# amp-PA-TQP7M9105-with-detect.net
KiCad netlist of a schematic drawn in EAGLE
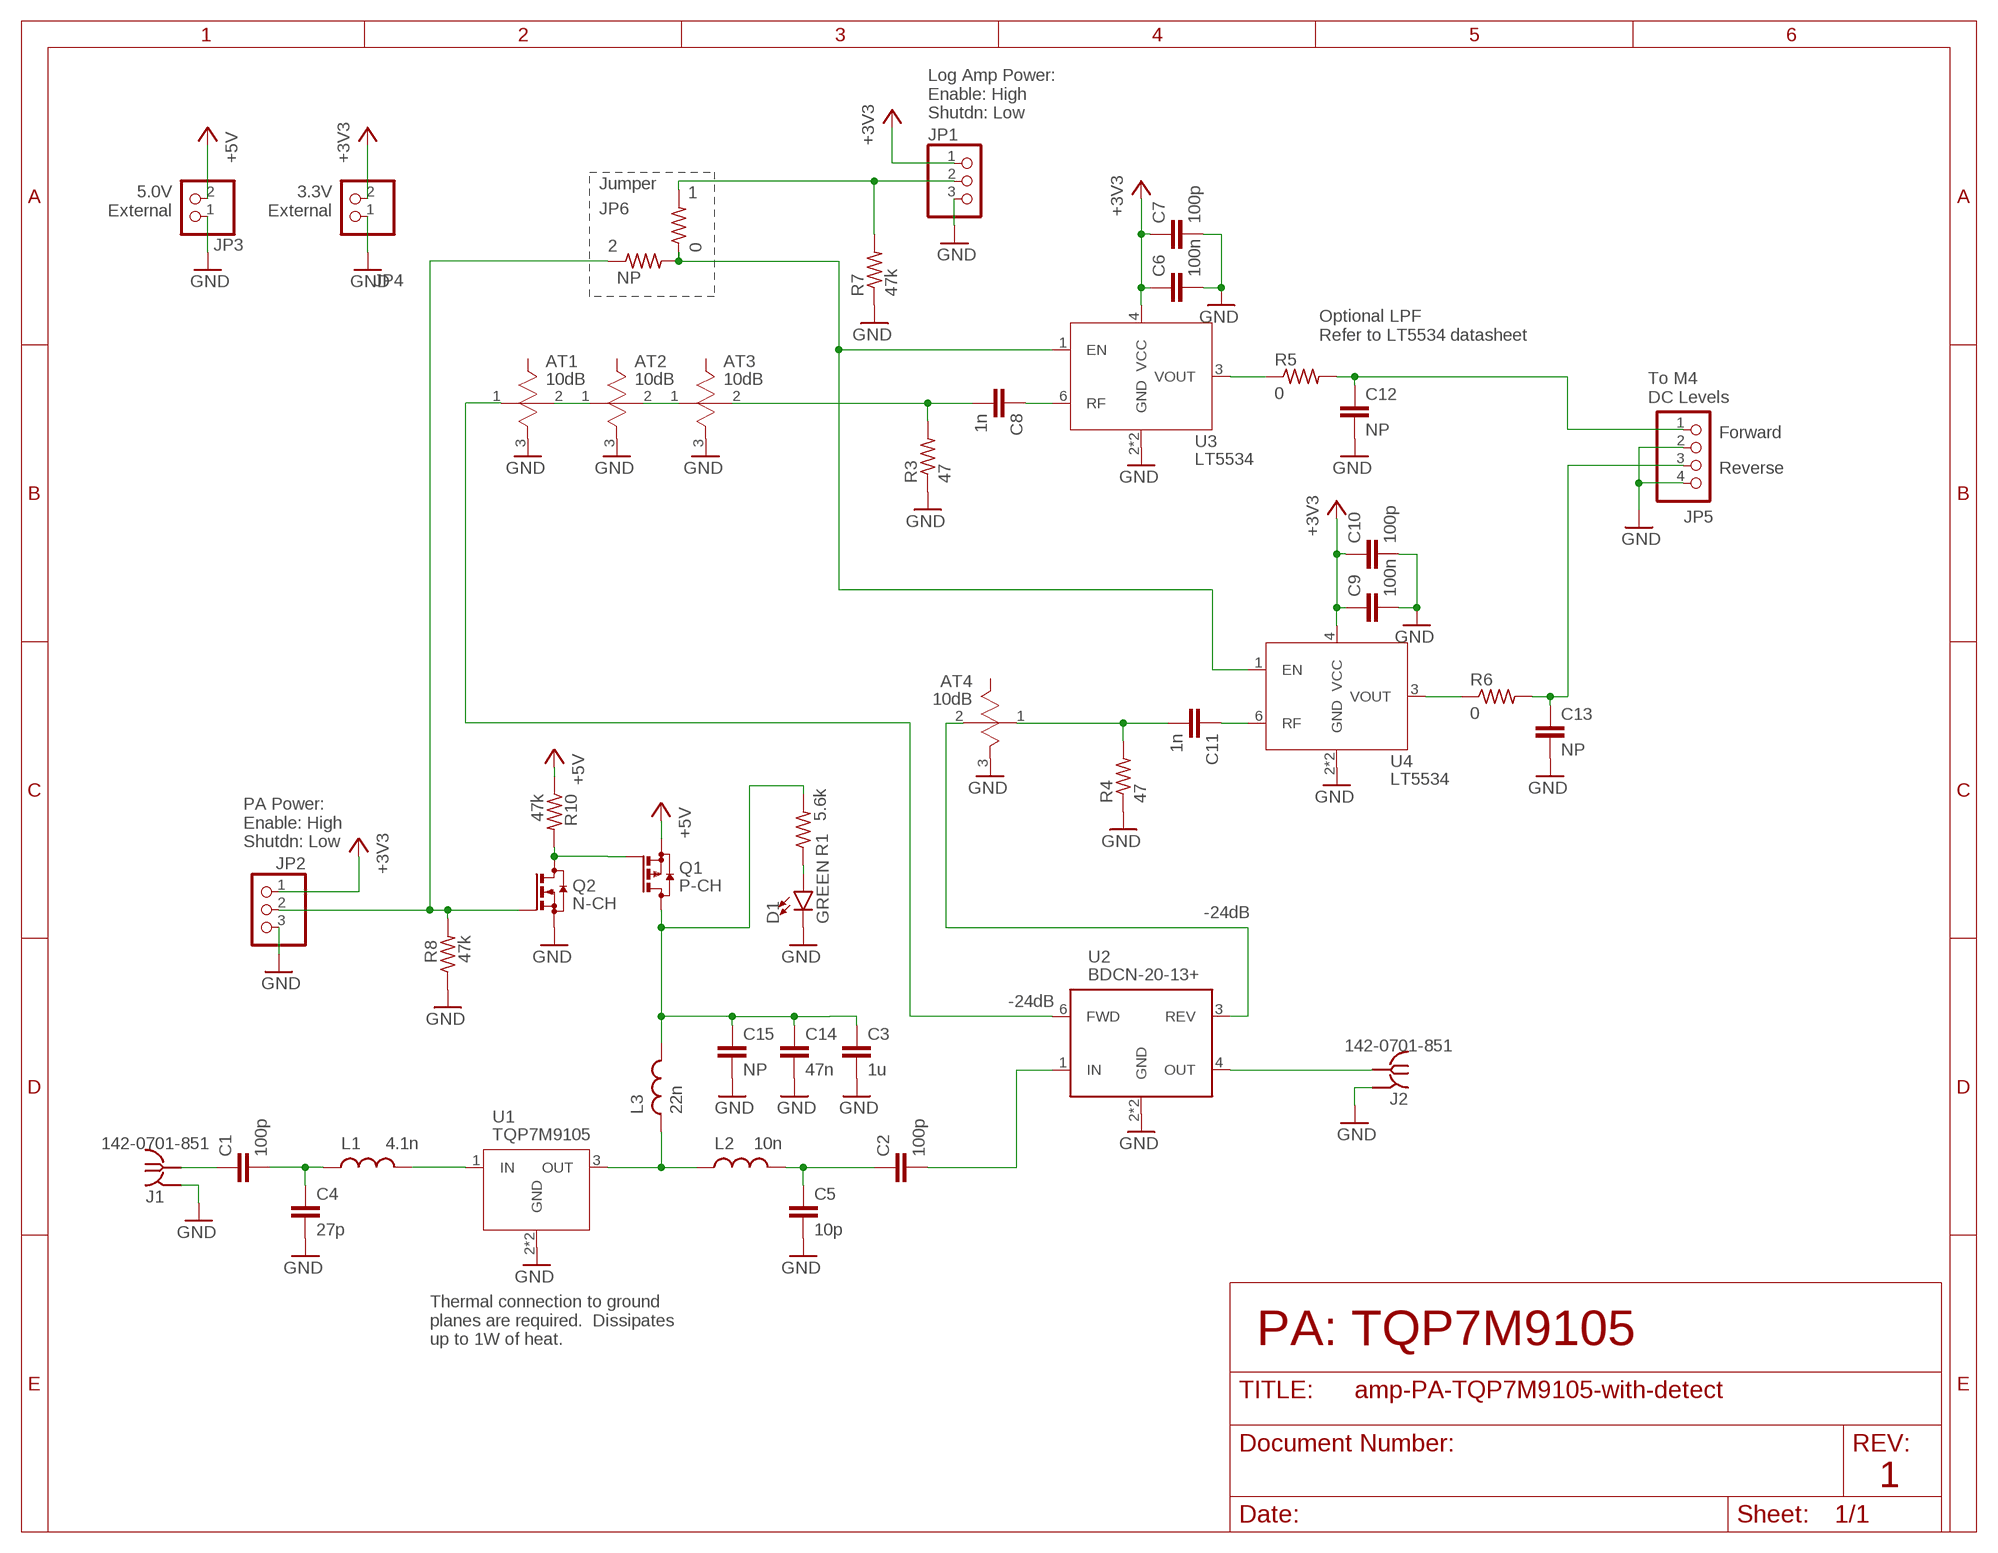
[diagram p0: schematic, sheet 1]

(export (version "E")
  (design (tool "Eeschema 10.0.6"))
  (components
    (comp (ref "AT1")
      (value "10dB")
      (footprint "eagle-import:0805")
      (libsource (lib "eagle-import") (part "PAT1220"))
    )
    (comp (ref "AT2")
      (value "10dB")
      (footprint "eagle-import:0603")
      (libsource (lib "eagle-import") (part "PAT0816"))
    )
    (comp (ref "AT3")
      (value "10dB")
      (footprint "eagle-import:0603")
      (libsource (lib "eagle-import") (part "PAT0816"))
    )
    (comp (ref "AT4")
      (value "10dB")
      (footprint "eagle-import:0603")
      (libsource (lib "eagle-import") (part "PAT0816"))
    )
    (comp (ref "C1")
      (value "100p")
      (footprint "eagle-import:.0402-C-NOSILK")
      (libsource (lib "eagle-import") (part "C-EU0402-C-NOSILK"))
    )
    (comp (ref "C2")
      (value "100p")
      (footprint "eagle-import:.0603-C-NOSILK")
      (libsource (lib "eagle-import") (part "C-EU0603-C-NOSILK"))
    )
    (comp (ref "C3")
      (value "1u")
      (footprint "eagle-import:.0603-B-NOSILK")
      (libsource (lib "eagle-import") (part "C-EU0603-B-NOSILK"))
    )
    (comp (ref "C4")
      (value "27p")
      (footprint "eagle-import:.0402-C-NOSILK")
      (libsource (lib "eagle-import") (part "C-EU0402-C-NOSILK"))
    )
    (comp (ref "C5")
      (value "10p")
      (footprint "eagle-import:.0603-C-NOSILK")
      (libsource (lib "eagle-import") (part "C-EU0603-C-NOSILK"))
    )
    (comp (ref "C6")
      (value "100n")
      (footprint "eagle-import:.0603-B-NOSILK")
      (libsource (lib "eagle-import") (part "C-EU0603-B-NOSILK"))
    )
    (comp (ref "C7")
      (value "100p")
      (footprint "eagle-import:.0603-B-NOSILK")
      (libsource (lib "eagle-import") (part "C-EU0603-B-NOSILK"))
    )
    (comp (ref "C8")
      (value "1n")
      (footprint "eagle-import:.0402-C-NOSILK")
      (libsource (lib "eagle-import") (part "C-EU0402-C-NOSILK"))
    )
    (comp (ref "C9")
      (value "100n")
      (footprint "eagle-import:.0603-B-NOSILK")
      (libsource (lib "eagle-import") (part "C-EU0603-B-NOSILK"))
    )
    (comp (ref "C10")
      (value "100p")
      (footprint "eagle-import:.0603-B-NOSILK")
      (libsource (lib "eagle-import") (part "C-EU0603-B-NOSILK"))
    )
    (comp (ref "C11")
      (value "1n")
      (footprint "eagle-import:.0402-C-NOSILK")
      (libsource (lib "eagle-import") (part "C-EU0402-C-NOSILK"))
    )
    (comp (ref "C12")
      (value "NP")
      (footprint "eagle-import:.0603-B-NOSILK")
      (libsource (lib "eagle-import") (part "C-EU0603-B-NOSILK"))
    )
    (comp (ref "C13")
      (value "NP")
      (footprint "eagle-import:.0603-B-NOSILK")
      (libsource (lib "eagle-import") (part "C-EU0603-B-NOSILK"))
    )
    (comp (ref "C14")
      (value "47n")
      (footprint "eagle-import:.0603-B-NOSILK")
      (libsource (lib "eagle-import") (part "C-EU0603-B-NOSILK"))
    )
    (comp (ref "C15")
      (value "NP")
      (footprint "eagle-import:.0603-B-NOSILK")
      (libsource (lib "eagle-import") (part "C-EU0603-B-NOSILK"))
    )
    (comp (ref "D1")
      (value "GREEN")
      (footprint "eagle-import:LED-0603")
      (libsource (lib "eagle-import") (part "LED-GREEN0603"))
    )
    (comp (ref "J1")
      (value "142-0701-851")
      (footprint "eagle-import:142-0701-851")
      (libsource (lib "eagle-import") (part "142-0701-851"))
    )
    (comp (ref "J2")
      (value "142-0701-851")
      (footprint "eagle-import:142-0701-851")
      (libsource (lib "eagle-import") (part "142-0701-851"))
    )
    (comp (ref "JP1")
      (value "PINHD-1X3")
      (footprint "eagle-import:1X03")
      (libsource (lib "eagle-import") (part "PINHD-1X3"))
    )
    (comp (ref "JP2")
      (value "PINHD-1X3")
      (footprint "eagle-import:1X03")
      (libsource (lib "eagle-import") (part "PINHD-1X3"))
    )
    (comp (ref "JP3")
      (value "PINHD-1X2")
      (footprint "eagle-import:1X02")
      (libsource (lib "eagle-import") (part "PINHD-1X2"))
    )
    (comp (ref "JP4")
      (value "PINHD-1X2")
      (footprint "eagle-import:1X02")
      (libsource (lib "eagle-import") (part "PINHD-1X2"))
    )
    (comp (ref "JP5")
      (value "PINHD-1X4")
      (footprint "eagle-import:1X04")
      (libsource (lib "eagle-import") (part "PINHD-1X4"))
    )
    (comp (ref "JP6")
      (value "NP")
      (footprint "eagle-import:.0603-B-NOSILK")
      (libsource (lib "eagle-import") (part "R-US_0603-B-NOSILK"))
    )
    (comp (ref "L1")
      (value "4.1n")
      (footprint "eagle-import:.0402-C-NOSILK")
      (libsource (lib "eagle-import") (part "L-US0402-C-NOSILK"))
    )
    (comp (ref "L2")
      (value "10n")
      (footprint "eagle-import:.0603-C-NOSILK@1")
      (libsource (lib "eagle-import") (part "L-US0603-C-NOSILK"))
    )
    (comp (ref "L3")
      (value "22n")
      (footprint "eagle-import:.0805-C-NOSILK")
      (libsource (lib "eagle-import") (part "L-US0805-C-NOSILK"))
    )
    (comp (ref "Q1")
      (value "P-CH")
      (footprint "eagle-import:SOT23")
      (libsource (lib "eagle-import") (part "BSS84"))
    )
    (comp (ref "Q2")
      (value "N-CH")
      (footprint "eagle-import:SOT23")
      (libsource (lib "eagle-import") (part "BSS123"))
    )
    (comp (ref "R1")
      (value "5.6k")
      (footprint "eagle-import:.0603-B-NOSILK")
      (libsource (lib "eagle-import") (part "R-US_0603-B-NOSILK"))
    )
    (comp (ref "R3")
      (value "47")
      (footprint "eagle-import:.0402-C-NOSILK")
      (libsource (lib "eagle-import") (part "R-US_0402-C-NOSILK"))
    )
    (comp (ref "R4")
      (value "47")
      (footprint "eagle-import:.0402-C-NOSILK")
      (libsource (lib "eagle-import") (part "R-US_0402-C-NOSILK"))
    )
    (comp (ref "R5")
      (value "0")
      (footprint "eagle-import:.0603-B-NOSILK")
      (libsource (lib "eagle-import") (part "R-US_0603-B-NOSILK"))
    )
    (comp (ref "R6")
      (value "0")
      (footprint "eagle-import:.0603-B-NOSILK")
      (libsource (lib "eagle-import") (part "R-US_0603-B-NOSILK"))
    )
    (comp (ref "R7")
      (value "47k")
      (footprint "eagle-import:.0402-B-NOSILK")
      (libsource (lib "eagle-import") (part "R-US_0402-B-NOSILK"))
    )
    (comp (ref "R8")
      (value "47k")
      (footprint "eagle-import:.0402-B-NOSILK")
      (libsource (lib "eagle-import") (part "R-US_0402-B-NOSILK"))
    )
    (comp (ref "R9")
      (value "0")
      (footprint "eagle-import:.0603-B-NOSILK")
      (libsource (lib "eagle-import") (part "R-US_0603-B-NOSILK"))
    )
    (comp (ref "R10")
      (value "47k")
      (footprint "eagle-import:.0402-B-NOSILK")
      (libsource (lib "eagle-import") (part "R-US_0402-B-NOSILK"))
    )
    (comp (ref "U1")
      (value "TQP7M9105")
      (footprint "eagle-import:TQP7M9105")
      (libsource (lib "eagle-import") (part "TQP7M9105"))
    )
    (comp (ref "U2")
      (value "BDCN-20-13+")
      (footprint "eagle-import:BDCN-20-13+")
      (libsource (lib "eagle-import") (part "BDCN-20-13+"))
    )
    (comp (ref "U3")
      (value "LT5534")
      (footprint "eagle-import:SC70")
      (libsource (lib "eagle-import") (part "LT5534"))
    )
    (comp (ref "U4")
      (value "LT5534")
      (footprint "eagle-import:SC70")
      (libsource (lib "eagle-import") (part "LT5534"))
    )
  )
  (nets
    (net (code "1") (name "+3V3") (class "Default")
      (node (ref "C10") (pin "1") (pinfunction "1_1") (pintype "passive"))
      (node (ref "C6") (pin "1") (pinfunction "1_1") (pintype "passive"))
      (node (ref "C7") (pin "1") (pinfunction "1_1") (pintype "passive"))
      (node (ref "C9") (pin "1") (pinfunction "1_1") (pintype "passive"))
      (node (ref "JP1") (pin "1") (pinfunction "1_1") (pintype "passive"))
      (node (ref "JP2") (pin "1") (pinfunction "1_1") (pintype "passive"))
      (node (ref "JP4") (pin "2") (pinfunction "2_2") (pintype "passive"))
      (node (ref "U3") (pin "4") (pinfunction "VCC_4") (pintype "power_in"))
      (node (ref "U4") (pin "4") (pinfunction "VCC_4") (pintype "power_in"))
    )
    (net (code "2") (name "+5V") (class "Default")
      (node (ref "JP3") (pin "2") (pinfunction "2_2") (pintype "passive"))
      (node (ref "Q1") (pin "2") (pinfunction "S_2") (pintype "passive"))
      (node (ref "R10") (pin "1") (pinfunction "1_1") (pintype "passive"))
    )
    (net (code "3") (name "GND") (class "Default")
      (node (ref "AT1") (pin "3") (pinfunction "GND_3") (pintype "power_in"))
      (node (ref "AT2") (pin "3") (pinfunction "GND_3") (pintype "power_in"))
      (node (ref "AT3") (pin "3") (pinfunction "GND_3") (pintype "power_in"))
      (node (ref "AT4") (pin "3") (pinfunction "GND_3") (pintype "power_in"))
      (node (ref "C10") (pin "2") (pinfunction "2_2") (pintype "passive"))
      (node (ref "C12") (pin "2") (pinfunction "2_2") (pintype "passive"))
      (node (ref "C13") (pin "2") (pinfunction "2_2") (pintype "passive"))
      (node (ref "C14") (pin "2") (pinfunction "2_2") (pintype "passive"))
      (node (ref "C15") (pin "2") (pinfunction "2_2") (pintype "passive"))
      (node (ref "C3") (pin "2") (pinfunction "2_2") (pintype "passive"))
      (node (ref "C4") (pin "2") (pinfunction "2_2") (pintype "passive"))
      (node (ref "C5") (pin "2") (pinfunction "2_2") (pintype "passive"))
      (node (ref "C6") (pin "2") (pinfunction "2_2") (pintype "passive"))
      (node (ref "C7") (pin "2") (pinfunction "2_2") (pintype "passive"))
      (node (ref "C9") (pin "2") (pinfunction "2_2") (pintype "passive"))
      (node (ref "D1") (pin "C") (pinfunction "C_C") (pintype "passive"))
      (node (ref "J1") (pin "GND1") (pinfunction "GND_GND1") (pintype "bidirectional"))
      (node (ref "J1") (pin "GND2") (pinfunction "GND_GND2") (pintype "bidirectional"))
      (node (ref "J1") (pin "GND3") (pinfunction "GND_GND3") (pintype "bidirectional"))
      (node (ref "J1") (pin "GND4") (pinfunction "GND_GND4") (pintype "bidirectional"))
      (node (ref "J2") (pin "GND1") (pinfunction "GND_GND1") (pintype "bidirectional"))
      (node (ref "J2") (pin "GND2") (pinfunction "GND_GND2") (pintype "bidirectional"))
      (node (ref "J2") (pin "GND3") (pinfunction "GND_GND3") (pintype "bidirectional"))
      (node (ref "J2") (pin "GND4") (pinfunction "GND_GND4") (pintype "bidirectional"))
      (node (ref "JP1") (pin "3") (pinfunction "3_3") (pintype "passive"))
      (node (ref "JP2") (pin "3") (pinfunction "3_3") (pintype "passive"))
      (node (ref "JP3") (pin "1") (pinfunction "1_1") (pintype "passive"))
      (node (ref "JP4") (pin "1") (pinfunction "1_1") (pintype "passive"))
      (node (ref "JP5") (pin "2") (pinfunction "2_2") (pintype "passive"))
      (node (ref "JP5") (pin "4") (pinfunction "4_4") (pintype "passive"))
      (node (ref "Q2") (pin "2") (pinfunction "S_2") (pintype "passive"))
      (node (ref "R3") (pin "1") (pinfunction "1_1") (pintype "passive"))
      (node (ref "R4") (pin "1") (pinfunction "1_1") (pintype "passive"))
      (node (ref "R7") (pin "1") (pinfunction "1_1") (pintype "passive"))
      (node (ref "R8") (pin "1") (pinfunction "1_1") (pintype "passive"))
      (node (ref "U1") (pin "2") (pinfunction "GND_2") (pintype "power_in"))
      (node (ref "U1") (pin "PAD") (pinfunction "GND_PAD") (pintype "power_in"))
      (node (ref "U2") (pin "2") (pinfunction "GND_2") (pintype "power_in"))
      (node (ref "U2") (pin "5") (pinfunction "GND_5") (pintype "power_in"))
      (node (ref "U3") (pin "2") (pinfunction "GND_2") (pintype "power_in"))
      (node (ref "U3") (pin "5") (pinfunction "GND_5") (pintype "power_in"))
      (node (ref "U4") (pin "2") (pinfunction "GND_2") (pintype "power_in"))
      (node (ref "U4") (pin "5") (pinfunction "GND_5") (pintype "power_in"))
    )
    (net (code "4") (name "Net-(AT1-Pad2)") (class "Default")
      (node (ref "AT1") (pin "2") (pinfunction "2_2") (pintype "bidirectional"))
      (node (ref "AT2") (pin "1") (pinfunction "1_1") (pintype "bidirectional"))
    )
    (net (code "5") (name "Net-(AT2-Pad2)") (class "Default")
      (node (ref "AT2") (pin "2") (pinfunction "2_2") (pintype "bidirectional"))
      (node (ref "AT3") (pin "1") (pinfunction "1_1") (pintype "bidirectional"))
    )
    (net (code "6") (name "Net-(AT3-Pad2)") (class "Default")
      (node (ref "AT3") (pin "2") (pinfunction "2_2") (pintype "bidirectional"))
      (node (ref "C8") (pin "2") (pinfunction "2_2") (pintype "passive"))
      (node (ref "R3") (pin "2") (pinfunction "2_2") (pintype "passive"))
    )
    (net (code "7") (name "Net-(AT4-Pad1)") (class "Default")
      (node (ref "AT4") (pin "1") (pinfunction "1_1") (pintype "bidirectional"))
      (node (ref "C11") (pin "2") (pinfunction "2_2") (pintype "passive"))
      (node (ref "R4") (pin "2") (pinfunction "2_2") (pintype "passive"))
    )
    (net (code "8") (name "Net-(C1-Pad2)") (class "Default")
      (node (ref "C1") (pin "2") (pinfunction "2_2") (pintype "passive"))
      (node (ref "C4") (pin "1") (pinfunction "1_1") (pintype "passive"))
      (node (ref "L1") (pin "1") (pinfunction "1_1") (pintype "passive"))
    )
    (net (code "9") (name "Net-(C2-Pad1)") (class "Default")
      (node (ref "C2") (pin "1") (pinfunction "1_1") (pintype "passive"))
      (node (ref "C5") (pin "1") (pinfunction "1_1") (pintype "passive"))
      (node (ref "L2") (pin "2") (pinfunction "2_2") (pintype "passive"))
    )
    (net (code "10") (name "Net-(C12-Pad1)") (class "Default")
      (node (ref "C12") (pin "1") (pinfunction "1_1") (pintype "passive"))
      (node (ref "JP5") (pin "1") (pinfunction "1_1") (pintype "passive"))
      (node (ref "R5") (pin "2") (pinfunction "2_2") (pintype "passive"))
    )
    (net (code "11") (name "Net-(C13-Pad1)") (class "Default")
      (node (ref "C13") (pin "1") (pinfunction "1_1") (pintype "passive"))
      (node (ref "JP5") (pin "3") (pinfunction "3_3") (pintype "passive"))
      (node (ref "R6") (pin "2") (pinfunction "2_2") (pintype "passive"))
    )
    (net (code "12") (name "Net-(D1-PadA)") (class "Default")
      (node (ref "D1") (pin "A") (pinfunction "A_A") (pintype "passive"))
      (node (ref "R1") (pin "1") (pinfunction "1_1") (pintype "passive"))
    )
    (net (code "13") (name "Net-(J1-RF)") (class "Default")
      (node (ref "C1") (pin "1") (pinfunction "1_1") (pintype "passive"))
      (node (ref "J1") (pin "RF1") (pinfunction "RF_RF1") (pintype "bidirectional"))
    )
    (net (code "14") (name "Net-(J2-RF)") (class "Default")
      (node (ref "J2") (pin "RF1") (pinfunction "RF_RF1") (pintype "bidirectional"))
      (node (ref "U2") (pin "4") (pinfunction "OUT_4") (pintype "output"))
    )
    (net (code "15") (name "Net-(JP1-Pad2)") (class "Default")
      (node (ref "JP1") (pin "2") (pinfunction "2_2") (pintype "passive"))
      (node (ref "R7") (pin "2") (pinfunction "2_2") (pintype "passive"))
      (node (ref "R9") (pin "2") (pinfunction "2_2") (pintype "passive"))
    )
    (net (code "16") (name "Net-(Q1-D)") (class "Default")
      (node (ref "C14") (pin "1") (pinfunction "1_1") (pintype "passive"))
      (node (ref "C15") (pin "1") (pinfunction "1_1") (pintype "passive"))
      (node (ref "C3") (pin "1") (pinfunction "1_1") (pintype "passive"))
      (node (ref "L3") (pin "2") (pinfunction "2_2") (pintype "passive"))
      (node (ref "Q1") (pin "3") (pinfunction "D_3") (pintype "passive"))
      (node (ref "R1") (pin "2") (pinfunction "2_2") (pintype "passive"))
    )
    (net (code "17") (name "Net-(Q1-G)") (class "Default")
      (node (ref "Q1") (pin "1") (pinfunction "G_1") (pintype "passive"))
      (node (ref "Q2") (pin "3") (pinfunction "D_3") (pintype "passive"))
      (node (ref "R10") (pin "2") (pinfunction "2_2") (pintype "passive"))
    )
    (net (code "18") (name "Net-(Q2-G)") (class "Default")
      (node (ref "JP2") (pin "2") (pinfunction "2_2") (pintype "passive"))
      (node (ref "JP6") (pin "1") (pinfunction "1_1") (pintype "passive"))
      (node (ref "Q2") (pin "1") (pinfunction "G_1") (pintype "passive"))
      (node (ref "R8") (pin "2") (pinfunction "2_2") (pintype "passive"))
    )
    (net (code "19") (name "Net-(U1-IN)") (class "Default")
      (node (ref "L1") (pin "2") (pinfunction "2_2") (pintype "passive"))
      (node (ref "U1") (pin "1") (pinfunction "IN_1") (pintype "bidirectional"))
    )
    (net (code "20") (name "Net-(U1-OUT)") (class "Default")
      (node (ref "L2") (pin "1") (pinfunction "1_1") (pintype "passive"))
      (node (ref "L3") (pin "1") (pinfunction "1_1") (pintype "passive"))
      (node (ref "U1") (pin "3") (pinfunction "OUT_3") (pintype "bidirectional"))
    )
    (net (code "21") (name "Net-(U2-FWD)") (class "Default")
      (node (ref "AT1") (pin "1") (pinfunction "1_1") (pintype "bidirectional"))
      (node (ref "U2") (pin "6") (pinfunction "FWD_6") (pintype "output"))
    )
    (net (code "22") (name "Net-(U2-IN)") (class "Default")
      (node (ref "C2") (pin "2") (pinfunction "2_2") (pintype "passive"))
      (node (ref "U2") (pin "1") (pinfunction "IN_1") (pintype "input"))
    )
    (net (code "23") (name "Net-(U2-REV)") (class "Default")
      (node (ref "AT4") (pin "2") (pinfunction "2_2") (pintype "bidirectional"))
      (node (ref "U2") (pin "3") (pinfunction "REV_3") (pintype "output"))
    )
    (net (code "24") (name "Net-(U3-EN)") (class "Default")
      (node (ref "JP6") (pin "2") (pinfunction "2_2") (pintype "passive"))
      (node (ref "R9") (pin "1") (pinfunction "1_1") (pintype "passive"))
      (node (ref "U3") (pin "1") (pinfunction "EN_1") (pintype "input"))
      (node (ref "U4") (pin "1") (pinfunction "EN_1") (pintype "input"))
    )
    (net (code "25") (name "Net-(U3-RF)") (class "Default")
      (node (ref "C8") (pin "1") (pinfunction "1_1") (pintype "passive"))
      (node (ref "U3") (pin "6") (pinfunction "RF_6") (pintype "input"))
    )
    (net (code "26") (name "Net-(U3-VOUT)") (class "Default")
      (node (ref "R5") (pin "1") (pinfunction "1_1") (pintype "passive"))
      (node (ref "U3") (pin "3") (pinfunction "VOUT_3") (pintype "output"))
    )
    (net (code "27") (name "Net-(U4-RF)") (class "Default")
      (node (ref "C11") (pin "1") (pinfunction "1_1") (pintype "passive"))
      (node (ref "U4") (pin "6") (pinfunction "RF_6") (pintype "input"))
    )
    (net (code "28") (name "Net-(U4-VOUT)") (class "Default")
      (node (ref "R6") (pin "1") (pinfunction "1_1") (pintype "passive"))
      (node (ref "U4") (pin "3") (pinfunction "VOUT_3") (pintype "output"))
    )
  )
)
